# DC_DC_V1_4_2-2_bottom.net
KiCad netlist of a schematic drawn in EAGLE
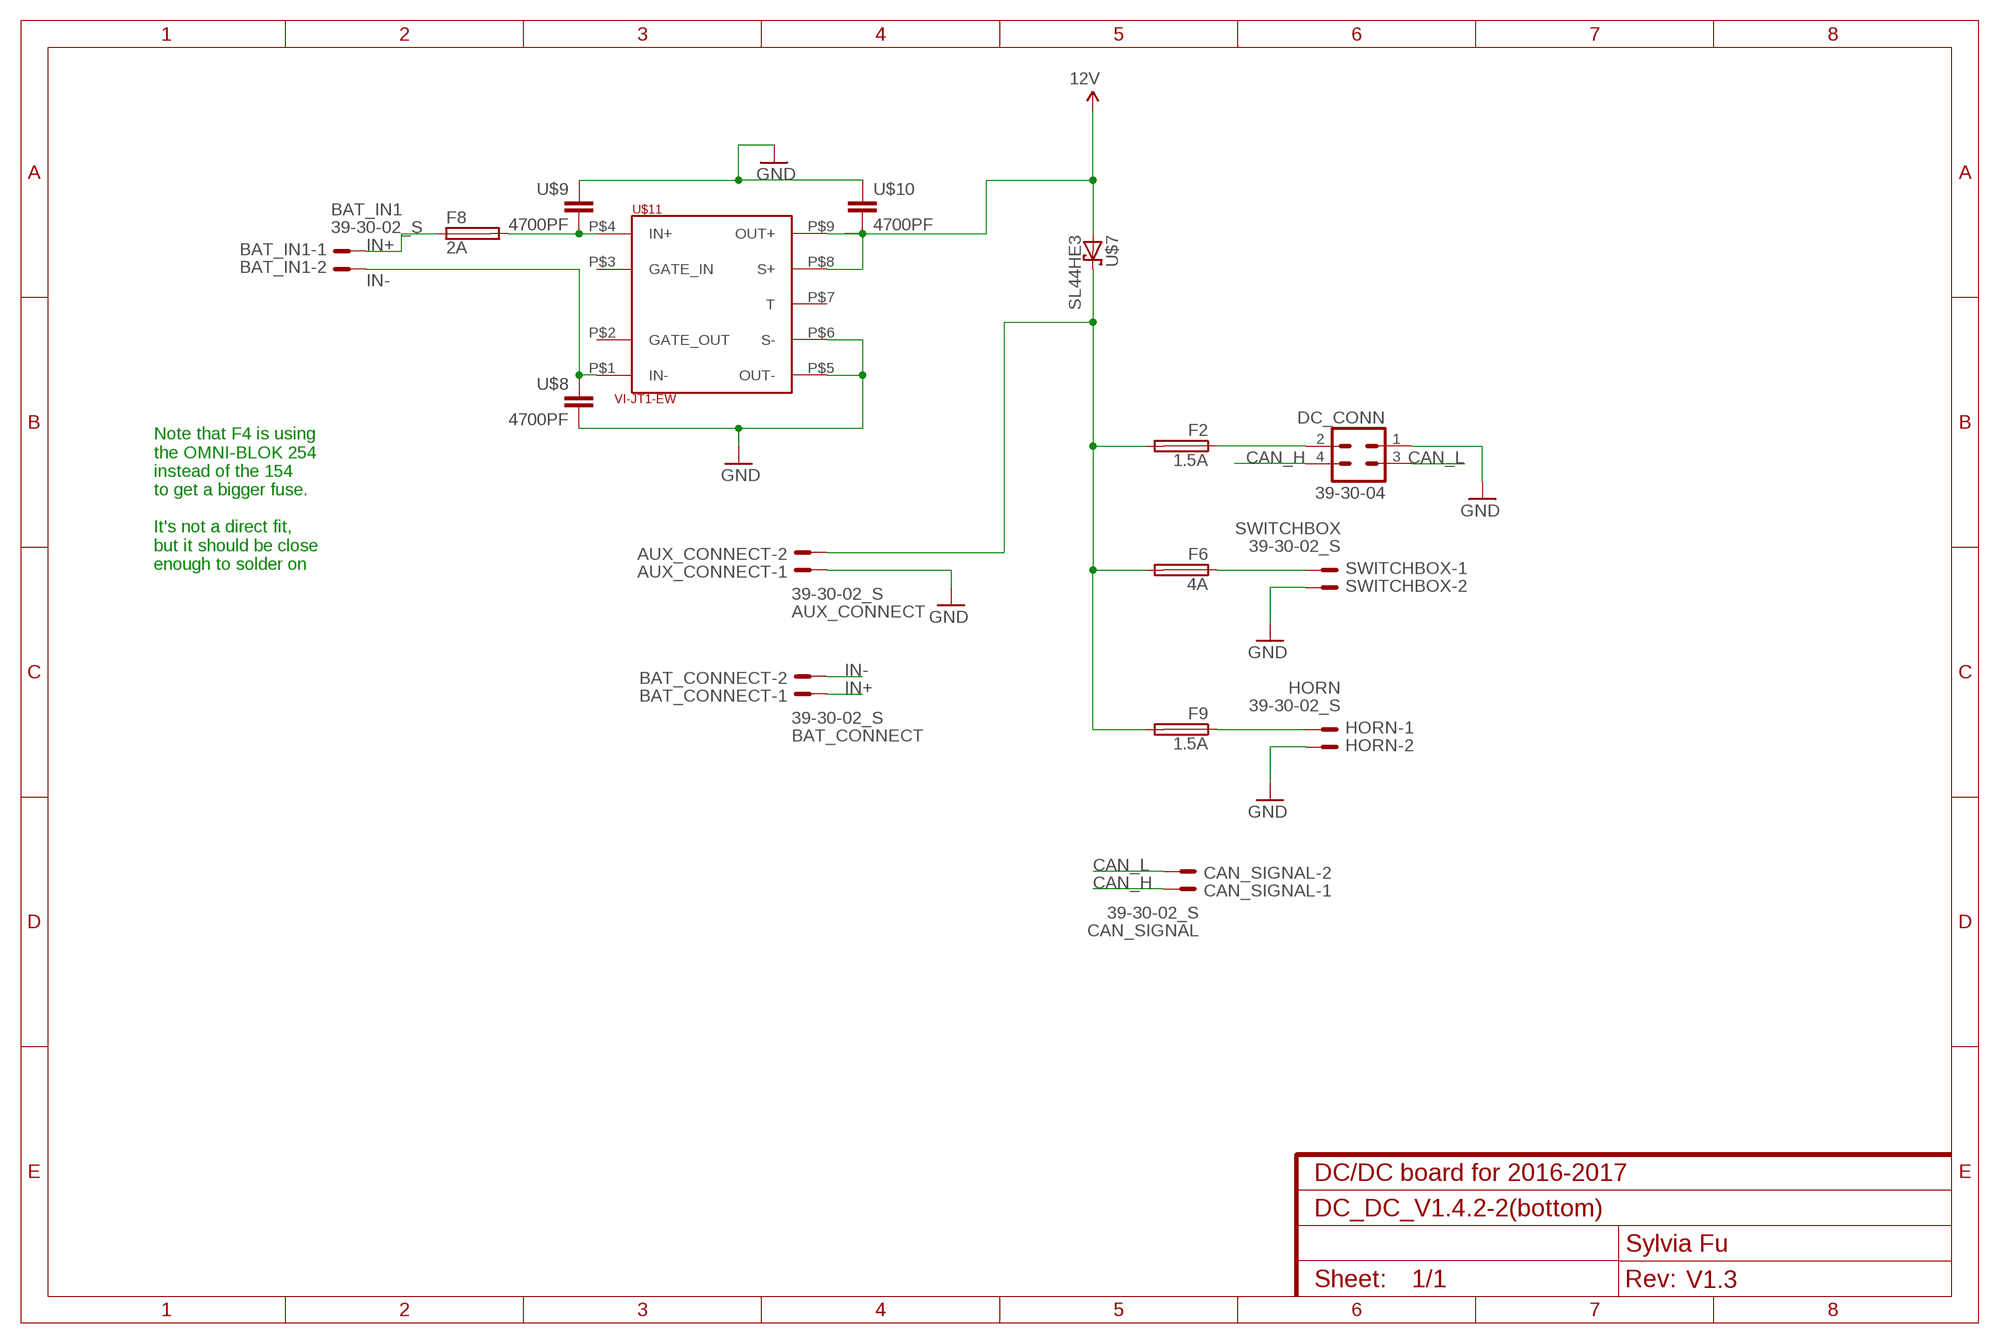
[diagram p0: schematic, sheet 1]

(export (version "E")
  (design (tool "Eeschema 10.0.6"))
  (components
    (comp (ref "AUX_CONNECT")
      (value "39-30-02_S")
      (footprint "eagle-import:39-30-_02_")
      (libsource (lib "eagle-import") (part "39-30-?02?_S"))
    )
    (comp (ref "BAT_CONNECT")
      (value "39-30-02_S")
      (footprint "eagle-import:39-30-_02_")
      (libsource (lib "eagle-import") (part "39-30-?02?_S"))
    )
    (comp (ref "BAT_IN1")
      (value "39-30-02_S")
      (footprint "eagle-import:39-30-_02_")
      (libsource (lib "eagle-import") (part "39-30-?02?_S"))
    )
    (comp (ref "CAN_SIGNAL")
      (value "39-30-02_S")
      (footprint "eagle-import:39-30-_02_")
      (libsource (lib "eagle-import") (part "39-30-?02?_S"))
    )
    (comp (ref "DC_CONN")
      (value "39-30-04")
      (footprint "eagle-import:39-30-_04_")
      (libsource (lib "eagle-import") (part "39-30-?04?"))
    )
    (comp (ref "F2")
      (value "1.5A")
      (footprint "eagle-import:OMNIBLOK")
      (libsource (lib "eagle-import") (part "SMD-MICRO-FUSE-BLOCK"))
    )
    (comp (ref "F6")
      (value "4A")
      (footprint "eagle-import:OMNIBLOK")
      (libsource (lib "eagle-import") (part "SMD-MICRO-FUSE-BLOCK"))
    )
    (comp (ref "F8")
      (value "2A")
      (footprint "eagle-import:OMNIBLOK")
      (libsource (lib "eagle-import") (part "SMD-MICRO-FUSE-BLOCK"))
    )
    (comp (ref "F9")
      (value "1.5A")
      (footprint "eagle-import:OMNIBLOK")
      (libsource (lib "eagle-import") (part "SMD-MICRO-FUSE-BLOCK"))
    )
    (comp (ref "HORN")
      (value "39-30-02_S")
      (footprint "eagle-import:39-30-_02_")
      (libsource (lib "eagle-import") (part "39-30-?02?_S"))
    )
    (comp (ref "SWITCHBOX")
      (value "39-30-02_S")
      (footprint "eagle-import:39-30-_02_")
      (libsource (lib "eagle-import") (part "39-30-?02?_S"))
    )
    (comp (ref "U$7")
      (value "SL44HE3")
      (footprint "eagle-import:SMC")
      (libsource (lib "eagle-import") (part "SL44HE3"))
    )
    (comp (ref "U$8")
      (value "4700PF")
      (footprint "eagle-import:Y2_CAP")
      (libsource (lib "eagle-import") (part "4700PF"))
    )
    (comp (ref "U$9")
      (value "4700PF")
      (footprint "eagle-import:Y2_CAP")
      (libsource (lib "eagle-import") (part "4700PF"))
    )
    (comp (ref "U$10")
      (value "4700PF")
      (footprint "eagle-import:Y2_CAP")
      (libsource (lib "eagle-import") (part "4700PF"))
    )
    (comp (ref "U$11")
      (value "VI-JT1-EW")
      (footprint "eagle-import:VI-J00")
      (libsource (lib "eagle-import") (part "VI-JT1-EW"))
    )
  )
  (nets
    (net (code "1") (name "/CAN_H") (class "Default")
      (node (ref "CAN_SIGNAL") (pin "1") (pinfunction "P_1") (pintype "passive"))
      (node (ref "DC_CONN") (pin "4") (pinfunction "4_4") (pintype "passive"))
    )
    (net (code "2") (name "/CAN_L") (class "Default")
      (node (ref "CAN_SIGNAL") (pin "2") (pinfunction "P_2") (pintype "passive"))
      (node (ref "DC_CONN") (pin "3") (pinfunction "3_3") (pintype "passive"))
    )
    (net (code "3") (name "/IN+") (class "Default")
      (node (ref "BAT_CONNECT") (pin "1") (pinfunction "P_1") (pintype "passive"))
      (node (ref "BAT_IN1") (pin "1") (pinfunction "P_1") (pintype "passive"))
      (node (ref "F8") (pin "P$1") (pinfunction "1_P$1") (pintype "passive"))
    )
    (net (code "4") (name "/IN-") (class "Default")
      (node (ref "BAT_CONNECT") (pin "2") (pinfunction "P_2") (pintype "passive"))
      (node (ref "BAT_IN1") (pin "2") (pinfunction "P_2") (pintype "passive"))
      (node (ref "U$11") (pin "P$1") (pinfunction "IN-_P$1") (pintype "bidirectional"))
      (node (ref "U$8") (pin "P$1") (pinfunction "1_P$1") (pintype "passive"))
    )
    (net (code "5") (name "12V") (class "Default")
      (node (ref "U$10") (pin "P$2") (pinfunction "2_P$2") (pintype "passive"))
      (node (ref "U$11") (pin "P$8") (pinfunction "S+_P$8") (pintype "bidirectional"))
      (node (ref "U$11") (pin "P$9") (pinfunction "OUT+_P$9") (pintype "bidirectional"))
      (node (ref "U$7") (pin "A") (pinfunction "A_A") (pintype "passive"))
    )
    (net (code "6") (name "GND") (class "Default")
      (node (ref "AUX_CONNECT") (pin "1") (pinfunction "P_1") (pintype "passive"))
      (node (ref "DC_CONN") (pin "1") (pinfunction "1_1") (pintype "passive"))
      (node (ref "HORN") (pin "2") (pinfunction "P_2") (pintype "passive"))
      (node (ref "SWITCHBOX") (pin "2") (pinfunction "P_2") (pintype "passive"))
      (node (ref "U$10") (pin "P$1") (pinfunction "1_P$1") (pintype "passive"))
      (node (ref "U$11") (pin "P$5") (pinfunction "OUT-_P$5") (pintype "bidirectional"))
      (node (ref "U$11") (pin "P$6") (pinfunction "S-_P$6") (pintype "bidirectional"))
      (node (ref "U$8") (pin "P$2") (pinfunction "2_P$2") (pintype "passive"))
      (node (ref "U$9") (pin "P$1") (pinfunction "1_P$1") (pintype "passive"))
    )
    (net (code "7") (name "Net-(AUX_CONNECTB-P)") (class "Default")
      (node (ref "AUX_CONNECT") (pin "2") (pinfunction "P_2") (pintype "passive"))
      (node (ref "F2") (pin "P$2") (pinfunction "2_P$2") (pintype "passive"))
      (node (ref "F6") (pin "P$2") (pinfunction "2_P$2") (pintype "passive"))
      (node (ref "F9") (pin "P$2") (pinfunction "2_P$2") (pintype "passive"))
      (node (ref "U$7") (pin "C") (pinfunction "C_C") (pintype "passive"))
    )
    (net (code "8") (name "Net-(F2-1)") (class "Default")
      (node (ref "DC_CONN") (pin "2") (pinfunction "2_2") (pintype "passive"))
      (node (ref "F2") (pin "P$1") (pinfunction "1_P$1") (pintype "passive"))
    )
    (net (code "9") (name "Net-(F6-1)") (class "Default")
      (node (ref "F6") (pin "P$1") (pinfunction "1_P$1") (pintype "passive"))
      (node (ref "SWITCHBOX") (pin "1") (pinfunction "P_1") (pintype "passive"))
    )
    (net (code "10") (name "Net-(F8-2)") (class "Default")
      (node (ref "F8") (pin "P$2") (pinfunction "2_P$2") (pintype "passive"))
      (node (ref "U$11") (pin "P$4") (pinfunction "IN+_P$4") (pintype "bidirectional"))
      (node (ref "U$9") (pin "P$2") (pinfunction "2_P$2") (pintype "passive"))
    )
    (net (code "11") (name "Net-(F9-1)") (class "Default")
      (node (ref "F9") (pin "P$1") (pinfunction "1_P$1") (pintype "passive"))
      (node (ref "HORN") (pin "1") (pinfunction "P_1") (pintype "passive"))
    )
    (net (code "12") (name "unconnected-(U$11-GATE_IN-PadP$3)") (class "Default")
      (node (ref "U$11") (pin "P$3") (pinfunction "GATE_IN_P$3") (pintype "bidirectional"))
    )
    (net (code "13") (name "unconnected-(U$11-GATE_OUT-PadP$2)") (class "Default")
      (node (ref "U$11") (pin "P$2") (pinfunction "GATE_OUT_P$2") (pintype "bidirectional"))
    )
    (net (code "14") (name "unconnected-(U$11-T-PadP$7)") (class "Default")
      (node (ref "U$11") (pin "P$7") (pinfunction "T_P$7") (pintype "bidirectional"))
    )
  )
)
